# CustComp_1_0.net
KiCad netlist of a schematic drawn in EAGLE
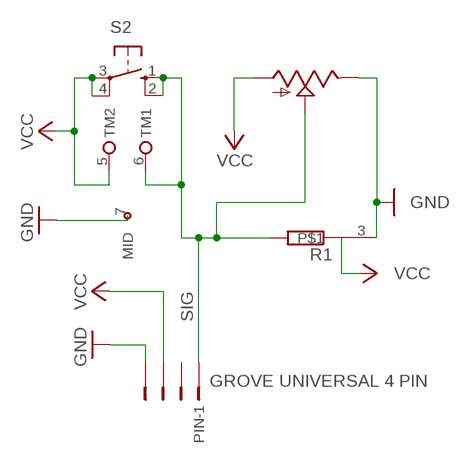
[diagram p0: schematic, sheet 1]

(export (version "E")
  (design (tool "Eeschema 10.0.6"))
  (components
    (comp (ref "PIN")
      (value "GROVE UNIVERSAL 4 PIN")
      (footprint "eagle-import:CON-JST_B4B-ZR")
      (fields (field (name "MF") "FARNELL") (field (name "MPN") "S4B-ZR(LF)(SN)"))
      (libsource (lib "eagle-import") (part "CON-JST_?4B-ZRB"))
    )
    (comp (ref "R1")
      (value "RES_PULL_UP_DOWNRES_PULL_UP_DOWN_ANGLE")
      (footprint "eagle-import:RES_PULL_UP_DOWN_ANGLE")
      (libsource (lib "eagle-import") (part "RES_PULL_UP_DOWNRES_PULL_UP_DOWN_ANGLE"))
    )
    (comp (ref "S2")
      (value "TERMINAL_TAC_SWITCH")
      (footprint "eagle-import:TERMINAL_TACTILE-PTH")
      (libsource (lib "eagle-import") (part "TERMINAL_TAC_SWITCH"))
    )
    (comp (ref "U$1")
      (value "SPARKFUN_POT")
      (footprint "eagle-import:SPARKFUN_ALPS_POT")
      (libsource (lib "eagle-import") (part "SPARKFUN_POT"))
    )
  )
  (nets
    (net (code "1") (name "/SIG") (class "Default")
      (node (ref "PIN") (pin "1") (pinfunction "1_1") (pintype "passive"))
      (node (ref "R1") (pin "1") (pinfunction "2_1") (pintype "passive"))
      (node (ref "S2") (pin "1") (pinfunction "3_1") (pintype "passive"))
      (node (ref "S2") (pin "2") (pinfunction "4_2") (pintype "passive"))
      (node (ref "S2") (pin "6") (pinfunction "TM1_6") (pintype "bidirectional"))
      (node (ref "U$1") (pin "P$2") (pinfunction "S_P$2") (pintype "passive"))
    )
    (net (code "2") (name "GND") (class "Default")
      (node (ref "PIN") (pin "4") (pinfunction "1_4") (pintype "passive"))
      (node (ref "R1") (pin "3") (pinfunction "P$1_3") (pintype "bidirectional"))
      (node (ref "S2") (pin "7") (pinfunction "MID_7") (pintype "bidirectional"))
      (node (ref "U$1") (pin "P$1") (pinfunction "E_P$1") (pintype "passive"))
    )
    (net (code "3") (name "VCC") (class "Default")
      (node (ref "PIN") (pin "3") (pinfunction "1_3") (pintype "passive"))
      (node (ref "R1") (pin "2") (pinfunction "1_2") (pintype "passive"))
      (node (ref "S2") (pin "3") (pinfunction "1_3") (pintype "passive"))
      (node (ref "S2") (pin "4") (pinfunction "2_4") (pintype "passive"))
      (node (ref "S2") (pin "5") (pinfunction "TM2_5") (pintype "bidirectional"))
      (node (ref "U$1") (pin "P$3") (pinfunction "A_P$3") (pintype "passive"))
    )
    (net (code "4") (name "unconnected-(PINB-1-Pad2)") (class "Default")
      (node (ref "PIN") (pin "2") (pinfunction "1_2") (pintype "passive"))
    )
  )
)
